# camera_final.net
KiCad netlist of a schematic drawn in EAGLE
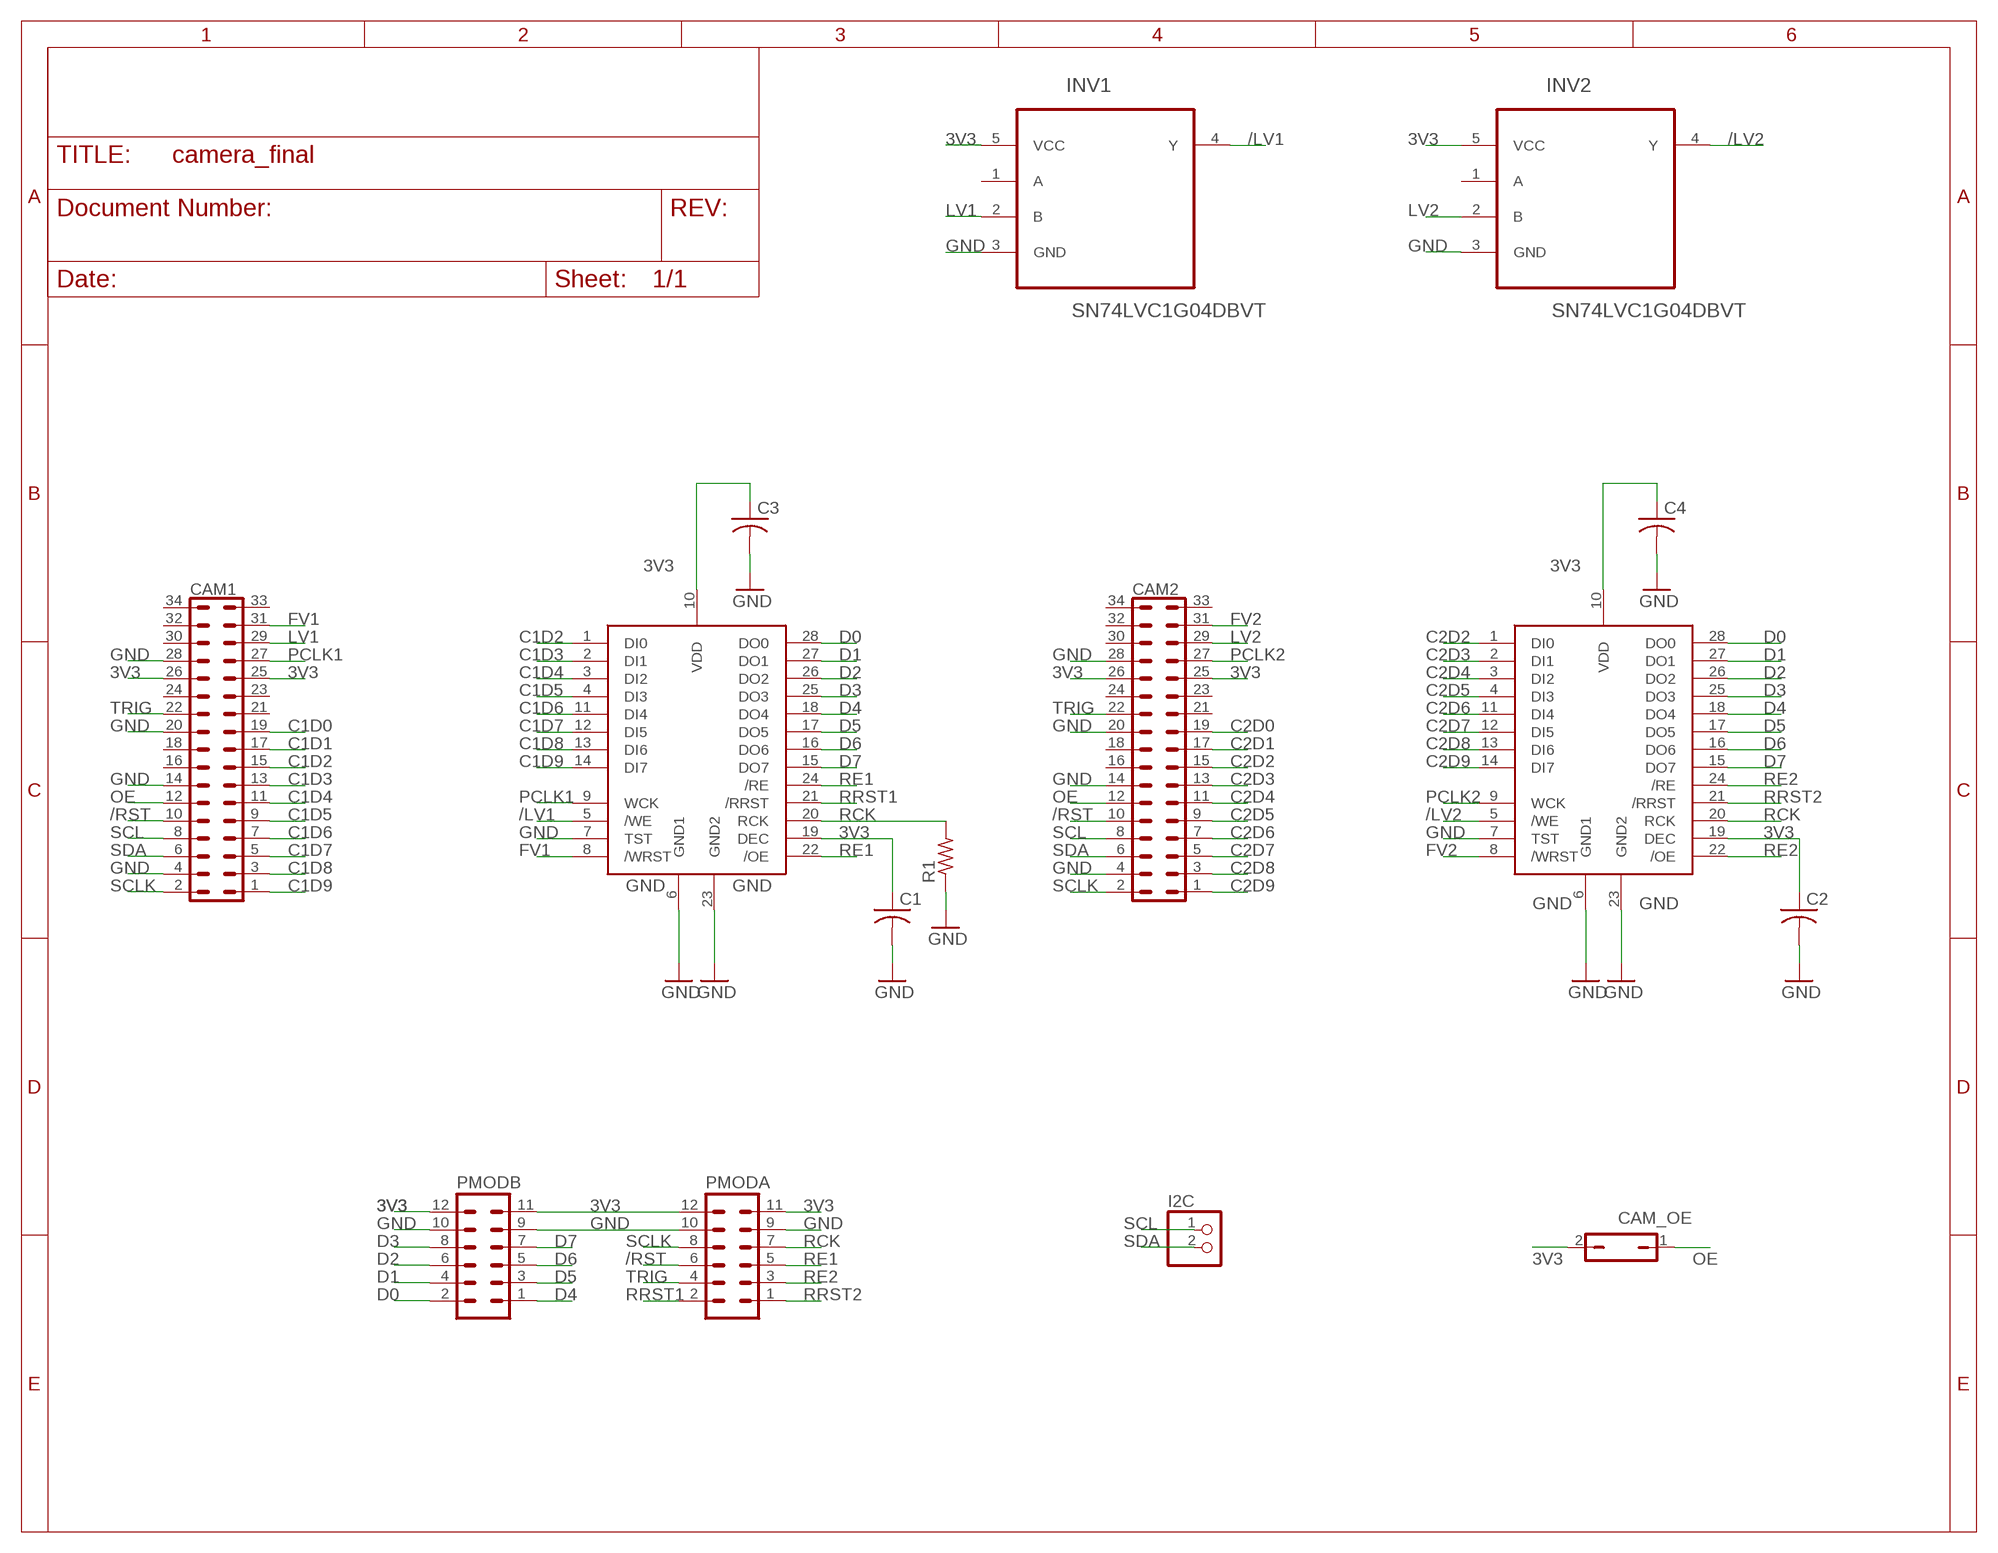
[diagram p0: schematic, sheet 1]

(export (version "E")
  (design (tool "Eeschema 10.0.6"))
  (components
    (comp (ref "C1")
      (value "C-USC0805K")
      (footprint "eagle-import:C0805K")
      (libsource (lib "eagle-import") (part "C-USC0805K"))
    )
    (comp (ref "C2")
      (value "C-USC0805K")
      (footprint "eagle-import:C0805K")
      (libsource (lib "eagle-import") (part "C-USC0805K"))
    )
    (comp (ref "C3")
      (value "C-USC0805K")
      (footprint "eagle-import:C0805K")
      (libsource (lib "eagle-import") (part "C-USC0805K"))
    )
    (comp (ref "C4")
      (value "C-USC0805K")
      (footprint "eagle-import:C0805K")
      (libsource (lib "eagle-import") (part "C-USC0805K"))
    )
    (comp (ref "CAM1")
      (value "PHB_1MM27_2X17_SNT")
      (footprint "eagle-import:PHB_1MM27_2X17_SNT")
      (libsource (lib "eagle-import") (part "PHB_1MM27_2X17_SNT"))
    )
    (comp (ref "CAM2")
      (value "PHB_1MM27_2X17_SNT")
      (footprint "eagle-import:PHB_1MM27_2X17_SNT")
      (libsource (lib "eagle-import") (part "PHB_1MM27_2X17_SNT"))
    )
    (comp (ref "CAM_OE")
      (value "JP1Q")
      (footprint "eagle-import:JP1")
      (libsource (lib "eagle-import") (part "JP1Q"))
    )
    (comp (ref "I2C")
      (value "PINHD-1X2")
      (footprint "eagle-import:1X02")
      (libsource (lib "eagle-import") (part "PINHD-1X2"))
    )
    (comp (ref "INV1")
      (value "SN74LVC1G04DBVT")
      (footprint "eagle-import:SOT95P280X145-5N")
      (fields (field (name "MPN") "SN74LVC1G08DBVT"))
      (libsource (lib "eagle-import") (part "SN74LVC1G08DBVT"))
    )
    (comp (ref "INV2")
      (value "SN74LVC1G04DBVT")
      (footprint "eagle-import:SOT95P280X145-5N")
      (fields (field (name "MPN") "SN74LVC1G08DBVT"))
      (libsource (lib "eagle-import") (part "SN74LVC1G08DBVT"))
    )
    (comp (ref "PMODA")
      (value "MA06-2")
      (footprint "eagle-import:MA06-2")
      (libsource (lib "eagle-import") (part "MA06-2"))
    )
    (comp (ref "PMODB")
      (value "MA06-2")
      (footprint "eagle-import:MA06-2")
      (libsource (lib "eagle-import") (part "MA06-2"))
    )
    (comp (ref "R1")
      (value "R-US_R0805")
      (footprint "eagle-import:R0805")
      (libsource (lib "eagle-import") (part "R-US_R0805"))
    )
    (comp (ref "U$1")
      (value "AL422B")
      (footprint "eagle-import:SOP28")
      (libsource (lib "eagle-import") (part "AL422B"))
    )
    (comp (ref "U$2")
      (value "AL422B")
      (footprint "eagle-import:SOP28")
      (libsource (lib "eagle-import") (part "AL422B"))
    )
  )
  (nets
    (net (code "1") (name "/3V3") (class "Default")
      (node (ref "C1") (pin "1") (pinfunction "1_1") (pintype "passive"))
      (node (ref "C2") (pin "1") (pinfunction "1_1") (pintype "passive"))
      (node (ref "C3") (pin "1") (pinfunction "1_1") (pintype "passive"))
      (node (ref "C4") (pin "1") (pinfunction "1_1") (pintype "passive"))
      (node (ref "CAM1") (pin "25") (pinfunction "25_25") (pintype "passive"))
      (node (ref "CAM1") (pin "26") (pinfunction "26_26") (pintype "passive"))
      (node (ref "CAM2") (pin "25") (pinfunction "25_25") (pintype "passive"))
      (node (ref "CAM2") (pin "26") (pinfunction "26_26") (pintype "passive"))
      (node (ref "CAM_OE") (pin "2") (pinfunction "2_2") (pintype "passive"))
      (node (ref "INV1") (pin "5") (pinfunction "VCC_5") (pintype "power_in"))
      (node (ref "INV2") (pin "5") (pinfunction "VCC_5") (pintype "power_in"))
      (node (ref "PMODA") (pin "11") (pinfunction "11_11") (pintype "passive"))
      (node (ref "PMODA") (pin "12") (pinfunction "12_12") (pintype "passive"))
      (node (ref "PMODB") (pin "11") (pinfunction "11_11") (pintype "passive"))
      (node (ref "PMODB") (pin "12") (pinfunction "12_12") (pintype "passive"))
      (node (ref "U$1") (pin "10") (pinfunction "VDD_10") (pintype "power_in"))
      (node (ref "U$1") (pin "19") (pinfunction "DEC_19") (pintype "bidirectional"))
      (node (ref "U$2") (pin "10") (pinfunction "VDD_10") (pintype "power_in"))
      (node (ref "U$2") (pin "19") (pinfunction "DEC_19") (pintype "bidirectional"))
    )
    (net (code "2") (name "/C1D0") (class "Default")
      (node (ref "CAM1") (pin "19") (pinfunction "19_19") (pintype "passive"))
    )
    (net (code "3") (name "/C1D1") (class "Default")
      (node (ref "CAM1") (pin "17") (pinfunction "17_17") (pintype "passive"))
    )
    (net (code "4") (name "/C1D2") (class "Default")
      (node (ref "CAM1") (pin "15") (pinfunction "15_15") (pintype "passive"))
      (node (ref "U$2") (pin "1") (pinfunction "DI0_1") (pintype "bidirectional"))
    )
    (net (code "5") (name "/C1D3") (class "Default")
      (node (ref "CAM1") (pin "13") (pinfunction "13_13") (pintype "passive"))
      (node (ref "U$2") (pin "2") (pinfunction "DI1_2") (pintype "bidirectional"))
    )
    (net (code "6") (name "/C1D4") (class "Default")
      (node (ref "CAM1") (pin "11") (pinfunction "11_11") (pintype "passive"))
      (node (ref "U$2") (pin "3") (pinfunction "DI2_3") (pintype "bidirectional"))
    )
    (net (code "7") (name "/C1D5") (class "Default")
      (node (ref "CAM1") (pin "9") (pinfunction "9_9") (pintype "passive"))
      (node (ref "U$2") (pin "4") (pinfunction "DI3_4") (pintype "bidirectional"))
    )
    (net (code "8") (name "/C1D6") (class "Default")
      (node (ref "CAM1") (pin "7") (pinfunction "7_7") (pintype "passive"))
      (node (ref "U$2") (pin "11") (pinfunction "DI4_11") (pintype "bidirectional"))
    )
    (net (code "9") (name "/C1D7") (class "Default")
      (node (ref "CAM1") (pin "5") (pinfunction "5_5") (pintype "passive"))
      (node (ref "U$2") (pin "12") (pinfunction "DI5_12") (pintype "bidirectional"))
    )
    (net (code "10") (name "/C1D8") (class "Default")
      (node (ref "CAM1") (pin "3") (pinfunction "3_3") (pintype "passive"))
      (node (ref "U$2") (pin "13") (pinfunction "DI6_13") (pintype "bidirectional"))
    )
    (net (code "11") (name "/C1D9") (class "Default")
      (node (ref "CAM1") (pin "1") (pinfunction "1_1") (pintype "passive"))
      (node (ref "U$2") (pin "14") (pinfunction "DI7_14") (pintype "bidirectional"))
    )
    (net (code "12") (name "/C2D0") (class "Default")
      (node (ref "CAM2") (pin "19") (pinfunction "19_19") (pintype "passive"))
    )
    (net (code "13") (name "/C2D1") (class "Default")
      (node (ref "CAM2") (pin "17") (pinfunction "17_17") (pintype "passive"))
    )
    (net (code "14") (name "/C2D2") (class "Default")
      (node (ref "CAM2") (pin "15") (pinfunction "15_15") (pintype "passive"))
      (node (ref "U$1") (pin "1") (pinfunction "DI0_1") (pintype "bidirectional"))
    )
    (net (code "15") (name "/C2D3") (class "Default")
      (node (ref "CAM2") (pin "13") (pinfunction "13_13") (pintype "passive"))
      (node (ref "U$1") (pin "2") (pinfunction "DI1_2") (pintype "bidirectional"))
    )
    (net (code "16") (name "/C2D4") (class "Default")
      (node (ref "CAM2") (pin "11") (pinfunction "11_11") (pintype "passive"))
      (node (ref "U$1") (pin "3") (pinfunction "DI2_3") (pintype "bidirectional"))
    )
    (net (code "17") (name "/C2D5") (class "Default")
      (node (ref "CAM2") (pin "9") (pinfunction "9_9") (pintype "passive"))
      (node (ref "U$1") (pin "4") (pinfunction "DI3_4") (pintype "bidirectional"))
    )
    (net (code "18") (name "/C2D6") (class "Default")
      (node (ref "CAM2") (pin "7") (pinfunction "7_7") (pintype "passive"))
      (node (ref "U$1") (pin "11") (pinfunction "DI4_11") (pintype "bidirectional"))
    )
    (net (code "19") (name "/C2D7") (class "Default")
      (node (ref "CAM2") (pin "5") (pinfunction "5_5") (pintype "passive"))
      (node (ref "U$1") (pin "12") (pinfunction "DI5_12") (pintype "bidirectional"))
    )
    (net (code "20") (name "/C2D8") (class "Default")
      (node (ref "CAM2") (pin "3") (pinfunction "3_3") (pintype "passive"))
      (node (ref "U$1") (pin "13") (pinfunction "DI6_13") (pintype "bidirectional"))
    )
    (net (code "21") (name "/C2D9") (class "Default")
      (node (ref "CAM2") (pin "1") (pinfunction "1_1") (pintype "passive"))
      (node (ref "U$1") (pin "14") (pinfunction "DI7_14") (pintype "bidirectional"))
    )
    (net (code "22") (name "/D0") (class "Default")
      (node (ref "PMODB") (pin "2") (pinfunction "2_2") (pintype "passive"))
      (node (ref "U$1") (pin "28") (pinfunction "DO0_28") (pintype "bidirectional"))
      (node (ref "U$2") (pin "28") (pinfunction "DO0_28") (pintype "bidirectional"))
    )
    (net (code "23") (name "/D1") (class "Default")
      (node (ref "PMODB") (pin "4") (pinfunction "4_4") (pintype "passive"))
      (node (ref "U$1") (pin "27") (pinfunction "DO1_27") (pintype "bidirectional"))
      (node (ref "U$2") (pin "27") (pinfunction "DO1_27") (pintype "bidirectional"))
    )
    (net (code "24") (name "/D2") (class "Default")
      (node (ref "PMODB") (pin "6") (pinfunction "6_6") (pintype "passive"))
      (node (ref "U$1") (pin "26") (pinfunction "DO2_26") (pintype "bidirectional"))
      (node (ref "U$2") (pin "26") (pinfunction "DO2_26") (pintype "bidirectional"))
    )
    (net (code "25") (name "/D3") (class "Default")
      (node (ref "PMODB") (pin "8") (pinfunction "8_8") (pintype "passive"))
      (node (ref "U$1") (pin "25") (pinfunction "DO3_25") (pintype "bidirectional"))
      (node (ref "U$2") (pin "25") (pinfunction "DO3_25") (pintype "bidirectional"))
    )
    (net (code "26") (name "/D4") (class "Default")
      (node (ref "PMODB") (pin "1") (pinfunction "1_1") (pintype "passive"))
      (node (ref "U$1") (pin "18") (pinfunction "DO4_18") (pintype "bidirectional"))
      (node (ref "U$2") (pin "18") (pinfunction "DO4_18") (pintype "bidirectional"))
    )
    (net (code "27") (name "/D5") (class "Default")
      (node (ref "PMODB") (pin "3") (pinfunction "3_3") (pintype "passive"))
      (node (ref "U$1") (pin "17") (pinfunction "DO5_17") (pintype "bidirectional"))
      (node (ref "U$2") (pin "17") (pinfunction "DO5_17") (pintype "bidirectional"))
    )
    (net (code "28") (name "/D6") (class "Default")
      (node (ref "PMODB") (pin "5") (pinfunction "5_5") (pintype "passive"))
      (node (ref "U$1") (pin "16") (pinfunction "DO6_16") (pintype "bidirectional"))
      (node (ref "U$2") (pin "16") (pinfunction "DO6_16") (pintype "bidirectional"))
    )
    (net (code "29") (name "/D7") (class "Default")
      (node (ref "PMODB") (pin "7") (pinfunction "7_7") (pintype "passive"))
      (node (ref "U$1") (pin "15") (pinfunction "DO7_15") (pintype "bidirectional"))
      (node (ref "U$2") (pin "15") (pinfunction "DO7_15") (pintype "bidirectional"))
    )
    (net (code "30") (name "/FV1") (class "Default")
      (node (ref "CAM1") (pin "31") (pinfunction "31_31") (pintype "passive"))
      (node (ref "U$2") (pin "8") (pinfunction "/WRST_8") (pintype "bidirectional"))
    )
    (net (code "31") (name "/FV2") (class "Default")
      (node (ref "CAM2") (pin "31") (pinfunction "31_31") (pintype "passive"))
      (node (ref "U$1") (pin "8") (pinfunction "/WRST_8") (pintype "bidirectional"))
    )
    (net (code "32") (name "/LV1") (class "Default")
      (node (ref "CAM1") (pin "29") (pinfunction "29_29") (pintype "passive"))
      (node (ref "INV1") (pin "2") (pinfunction "B_2") (pintype "input"))
    )
    (net (code "33") (name "/LV2") (class "Default")
      (node (ref "CAM2") (pin "29") (pinfunction "29_29") (pintype "passive"))
      (node (ref "INV2") (pin "2") (pinfunction "B_2") (pintype "input"))
    )
    (net (code "34") (name "/OE") (class "Default")
      (node (ref "CAM1") (pin "12") (pinfunction "12_12") (pintype "passive"))
      (node (ref "CAM2") (pin "12") (pinfunction "12_12") (pintype "passive"))
      (node (ref "CAM_OE") (pin "1") (pinfunction "1_1") (pintype "passive"))
    )
    (net (code "35") (name "/PCLK1") (class "Default")
      (node (ref "CAM1") (pin "27") (pinfunction "27_27") (pintype "passive"))
      (node (ref "U$2") (pin "9") (pinfunction "WCK_9") (pintype "bidirectional"))
    )
    (net (code "36") (name "/PCLK2") (class "Default")
      (node (ref "CAM2") (pin "27") (pinfunction "27_27") (pintype "passive"))
      (node (ref "U$1") (pin "9") (pinfunction "WCK_9") (pintype "bidirectional"))
    )
    (net (code "37") (name "/RCK") (class "Default")
      (node (ref "PMODA") (pin "7") (pinfunction "7_7") (pintype "passive"))
      (node (ref "R1") (pin "2") (pinfunction "2_2") (pintype "passive"))
      (node (ref "U$1") (pin "20") (pinfunction "RCK_20") (pintype "bidirectional"))
      (node (ref "U$2") (pin "20") (pinfunction "RCK_20") (pintype "bidirectional"))
    )
    (net (code "38") (name "/RE1") (class "Default")
      (node (ref "PMODA") (pin "5") (pinfunction "5_5") (pintype "passive"))
      (node (ref "U$2") (pin "22") (pinfunction "/OE_22") (pintype "bidirectional"))
      (node (ref "U$2") (pin "24") (pinfunction "/RE_24") (pintype "bidirectional"))
    )
    (net (code "39") (name "/RE2") (class "Default")
      (node (ref "PMODA") (pin "3") (pinfunction "3_3") (pintype "passive"))
      (node (ref "U$1") (pin "22") (pinfunction "/OE_22") (pintype "bidirectional"))
      (node (ref "U$1") (pin "24") (pinfunction "/RE_24") (pintype "bidirectional"))
    )
    (net (code "40") (name "/RRST1") (class "Default")
      (node (ref "PMODA") (pin "2") (pinfunction "2_2") (pintype "passive"))
      (node (ref "U$2") (pin "21") (pinfunction "/RRST_21") (pintype "bidirectional"))
    )
    (net (code "41") (name "/RRST2") (class "Default")
      (node (ref "PMODA") (pin "1") (pinfunction "1_1") (pintype "passive"))
      (node (ref "U$1") (pin "21") (pinfunction "/RRST_21") (pintype "bidirectional"))
    )
    (net (code "42") (name "/SCL") (class "Default")
      (node (ref "CAM1") (pin "8") (pinfunction "8_8") (pintype "passive"))
      (node (ref "CAM2") (pin "8") (pinfunction "8_8") (pintype "passive"))
      (node (ref "I2C") (pin "1") (pinfunction "1_1") (pintype "passive"))
    )
    (net (code "43") (name "/SCLK") (class "Default")
      (node (ref "CAM1") (pin "2") (pinfunction "2_2") (pintype "passive"))
      (node (ref "CAM2") (pin "2") (pinfunction "2_2") (pintype "passive"))
      (node (ref "PMODA") (pin "8") (pinfunction "8_8") (pintype "passive"))
    )
    (net (code "44") (name "/SDA") (class "Default")
      (node (ref "CAM1") (pin "6") (pinfunction "6_6") (pintype "passive"))
      (node (ref "CAM2") (pin "6") (pinfunction "6_6") (pintype "passive"))
      (node (ref "I2C") (pin "2") (pinfunction "2_2") (pintype "passive"))
    )
    (net (code "45") (name "/TRIG") (class "Default")
      (node (ref "CAM1") (pin "22") (pinfunction "22_22") (pintype "passive"))
      (node (ref "CAM2") (pin "22") (pinfunction "22_22") (pintype "passive"))
      (node (ref "PMODA") (pin "4") (pinfunction "4_4") (pintype "passive"))
    )
    (net (code "46") (name "/{slash}LV1") (class "Default")
      (node (ref "INV1") (pin "4") (pinfunction "Y_4") (pintype "output"))
      (node (ref "U$2") (pin "5") (pinfunction "/WE_5") (pintype "bidirectional"))
    )
    (net (code "47") (name "/{slash}LV2") (class "Default")
      (node (ref "INV2") (pin "4") (pinfunction "Y_4") (pintype "output"))
      (node (ref "U$1") (pin "5") (pinfunction "/WE_5") (pintype "bidirectional"))
    )
    (net (code "48") (name "/{slash}RST") (class "Default")
      (node (ref "CAM1") (pin "10") (pinfunction "10_10") (pintype "passive"))
      (node (ref "CAM2") (pin "10") (pinfunction "10_10") (pintype "passive"))
      (node (ref "PMODA") (pin "6") (pinfunction "6_6") (pintype "passive"))
    )
    (net (code "49") (name "GND") (class "Default")
      (node (ref "C1") (pin "2") (pinfunction "2_2") (pintype "passive"))
      (node (ref "C2") (pin "2") (pinfunction "2_2") (pintype "passive"))
      (node (ref "C3") (pin "2") (pinfunction "2_2") (pintype "passive"))
      (node (ref "C4") (pin "2") (pinfunction "2_2") (pintype "passive"))
      (node (ref "CAM1") (pin "14") (pinfunction "14_14") (pintype "passive"))
      (node (ref "CAM1") (pin "20") (pinfunction "20_20") (pintype "passive"))
      (node (ref "CAM1") (pin "28") (pinfunction "28_28") (pintype "passive"))
      (node (ref "CAM1") (pin "4") (pinfunction "4_4") (pintype "passive"))
      (node (ref "CAM2") (pin "14") (pinfunction "14_14") (pintype "passive"))
      (node (ref "CAM2") (pin "20") (pinfunction "20_20") (pintype "passive"))
      (node (ref "CAM2") (pin "28") (pinfunction "28_28") (pintype "passive"))
      (node (ref "CAM2") (pin "4") (pinfunction "4_4") (pintype "passive"))
      (node (ref "INV1") (pin "3") (pinfunction "GND_3") (pintype "passive"))
      (node (ref "INV2") (pin "3") (pinfunction "GND_3") (pintype "passive"))
      (node (ref "PMODA") (pin "10") (pinfunction "10_10") (pintype "passive"))
      (node (ref "PMODA") (pin "9") (pinfunction "9_9") (pintype "passive"))
      (node (ref "PMODB") (pin "10") (pinfunction "10_10") (pintype "passive"))
      (node (ref "PMODB") (pin "9") (pinfunction "9_9") (pintype "passive"))
      (node (ref "R1") (pin "1") (pinfunction "1_1") (pintype "passive"))
      (node (ref "U$1") (pin "23") (pinfunction "GND2_23") (pintype "power_in"))
      (node (ref "U$1") (pin "6") (pinfunction "GND1_6") (pintype "power_in"))
      (node (ref "U$1") (pin "7") (pinfunction "TST_7") (pintype "bidirectional"))
      (node (ref "U$2") (pin "23") (pinfunction "GND2_23") (pintype "power_in"))
      (node (ref "U$2") (pin "6") (pinfunction "GND1_6") (pintype "power_in"))
      (node (ref "U$2") (pin "7") (pinfunction "TST_7") (pintype "bidirectional"))
    )
    (net (code "50") (name "unconnected-(CAM1-Pad16)") (class "Default")
      (node (ref "CAM1") (pin "16") (pinfunction "16_16") (pintype "passive"))
    )
    (net (code "51") (name "unconnected-(CAM1-Pad18)") (class "Default")
      (node (ref "CAM1") (pin "18") (pinfunction "18_18") (pintype "passive"))
    )
    (net (code "52") (name "unconnected-(CAM1-Pad21)") (class "Default")
      (node (ref "CAM1") (pin "21") (pinfunction "21_21") (pintype "passive"))
    )
    (net (code "53") (name "unconnected-(CAM1-Pad23)") (class "Default")
      (node (ref "CAM1") (pin "23") (pinfunction "23_23") (pintype "passive"))
    )
    (net (code "54") (name "unconnected-(CAM1-Pad24)") (class "Default")
      (node (ref "CAM1") (pin "24") (pinfunction "24_24") (pintype "passive"))
    )
    (net (code "55") (name "unconnected-(CAM1-Pad30)") (class "Default")
      (node (ref "CAM1") (pin "30") (pinfunction "30_30") (pintype "passive"))
    )
    (net (code "56") (name "unconnected-(CAM1-Pad32)") (class "Default")
      (node (ref "CAM1") (pin "32") (pinfunction "32_32") (pintype "passive"))
    )
    (net (code "57") (name "unconnected-(CAM1-Pad33)") (class "Default")
      (node (ref "CAM1") (pin "33") (pinfunction "33_33") (pintype "passive"))
    )
    (net (code "58") (name "unconnected-(CAM1-Pad34)") (class "Default")
      (node (ref "CAM1") (pin "34") (pinfunction "34_34") (pintype "passive"))
    )
    (net (code "59") (name "unconnected-(CAM2-Pad16)") (class "Default")
      (node (ref "CAM2") (pin "16") (pinfunction "16_16") (pintype "passive"))
    )
    (net (code "60") (name "unconnected-(CAM2-Pad18)") (class "Default")
      (node (ref "CAM2") (pin "18") (pinfunction "18_18") (pintype "passive"))
    )
    (net (code "61") (name "unconnected-(CAM2-Pad21)") (class "Default")
      (node (ref "CAM2") (pin "21") (pinfunction "21_21") (pintype "passive"))
    )
    (net (code "62") (name "unconnected-(CAM2-Pad23)") (class "Default")
      (node (ref "CAM2") (pin "23") (pinfunction "23_23") (pintype "passive"))
    )
    (net (code "63") (name "unconnected-(CAM2-Pad24)") (class "Default")
      (node (ref "CAM2") (pin "24") (pinfunction "24_24") (pintype "passive"))
    )
    (net (code "64") (name "unconnected-(CAM2-Pad30)") (class "Default")
      (node (ref "CAM2") (pin "30") (pinfunction "30_30") (pintype "passive"))
    )
    (net (code "65") (name "unconnected-(CAM2-Pad32)") (class "Default")
      (node (ref "CAM2") (pin "32") (pinfunction "32_32") (pintype "passive"))
    )
    (net (code "66") (name "unconnected-(CAM2-Pad33)") (class "Default")
      (node (ref "CAM2") (pin "33") (pinfunction "33_33") (pintype "passive"))
    )
    (net (code "67") (name "unconnected-(CAM2-Pad34)") (class "Default")
      (node (ref "CAM2") (pin "34") (pinfunction "34_34") (pintype "passive"))
    )
    (net (code "68") (name "unconnected-(INV1-A-Pad1)") (class "Default")
      (node (ref "INV1") (pin "1") (pinfunction "A_1") (pintype "input"))
    )
    (net (code "69") (name "unconnected-(INV2-A-Pad1)") (class "Default")
      (node (ref "INV2") (pin "1") (pinfunction "A_1") (pintype "input"))
    )
  )
)
